# Due_Shield_v1_0.net
KiCad netlist of a schematic drawn in EAGLE
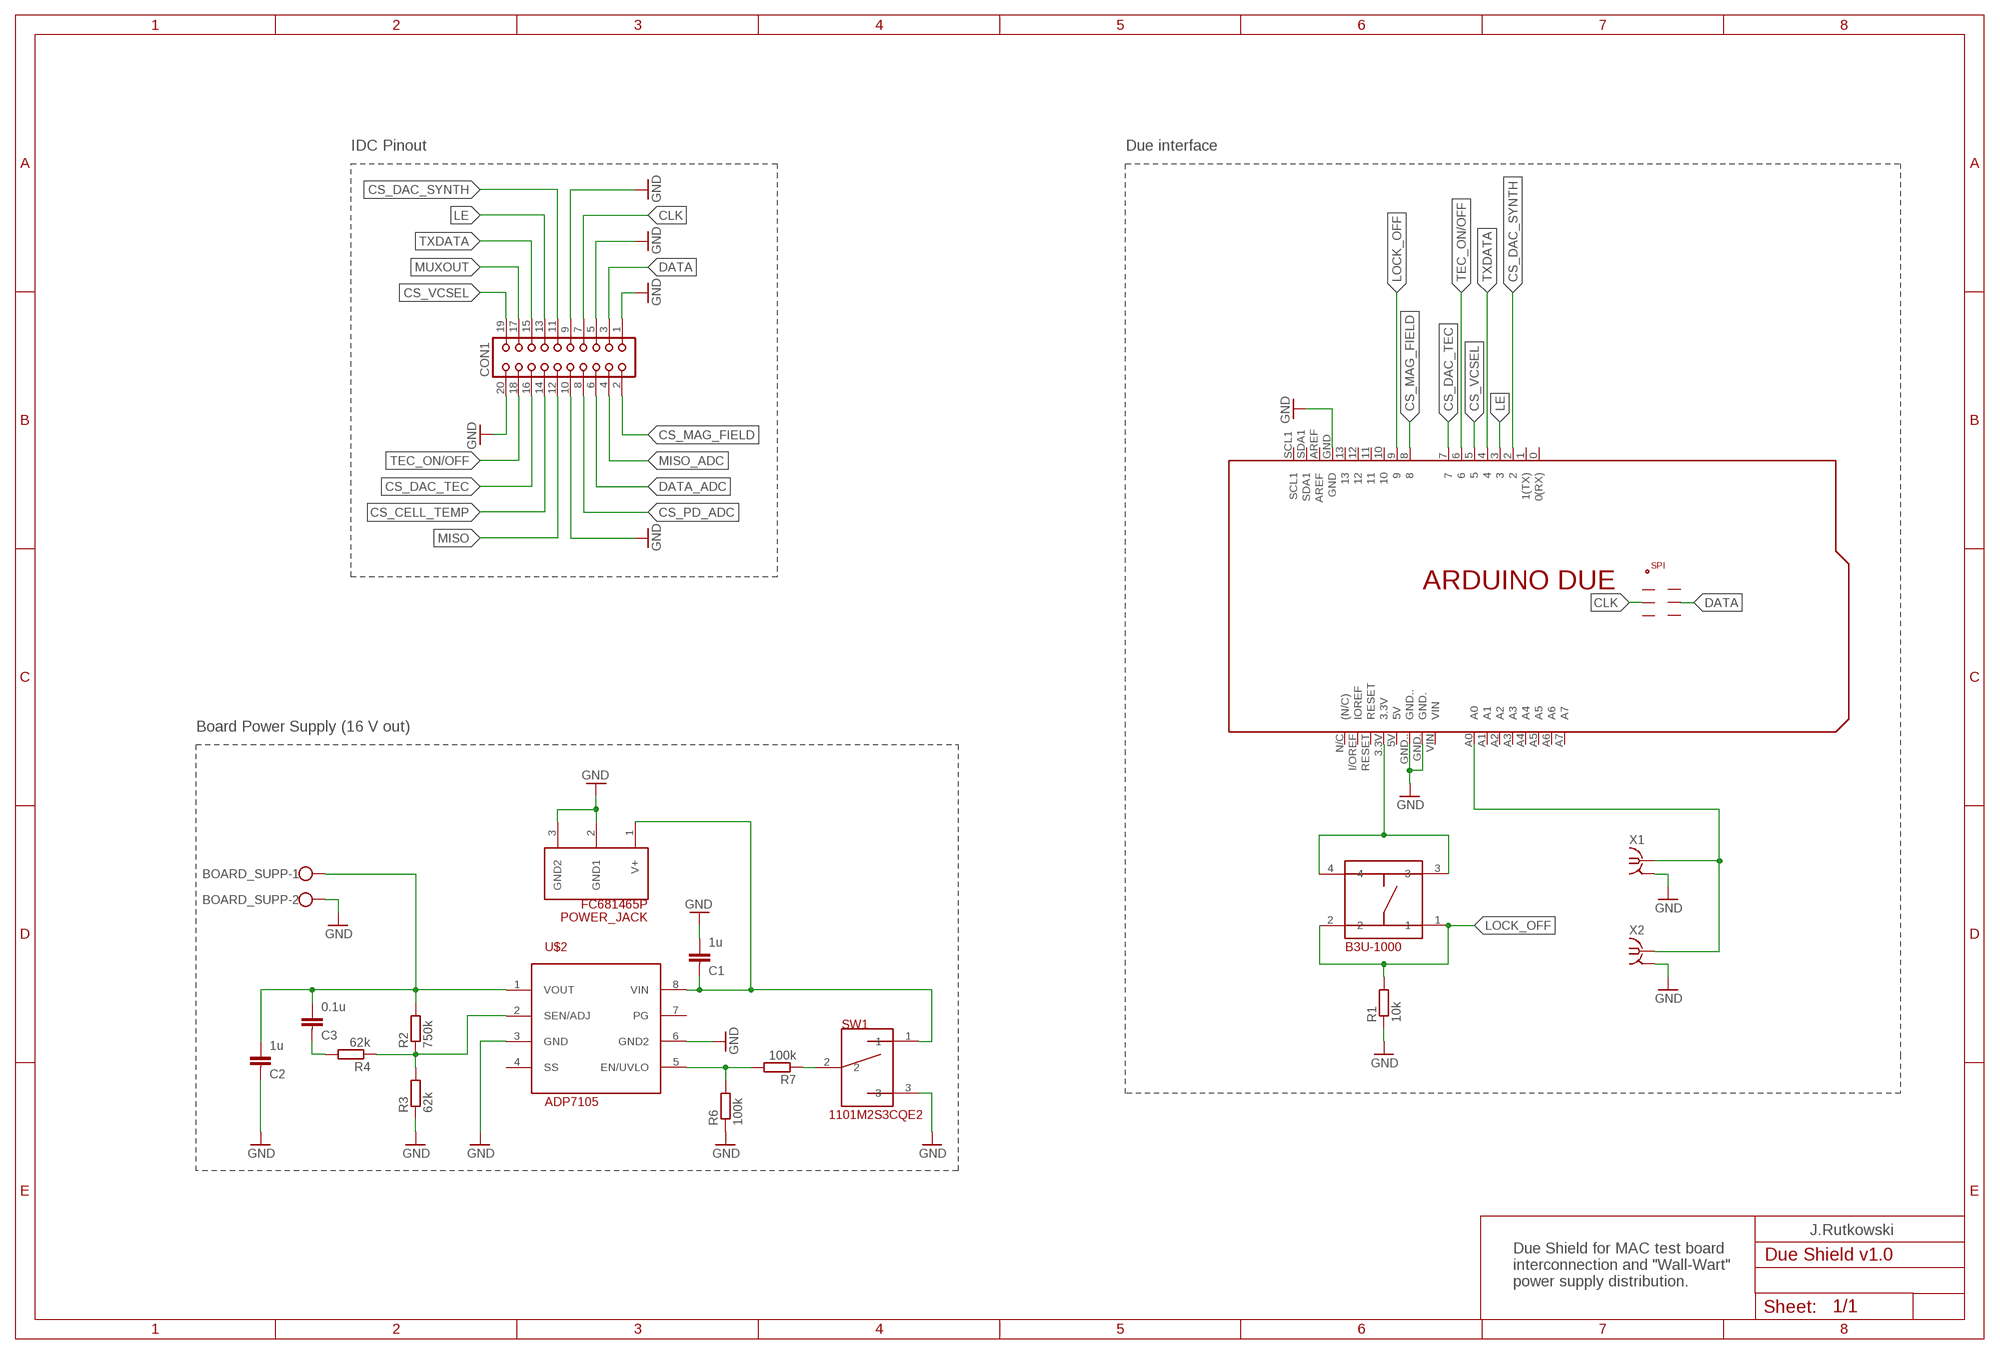
[diagram p0: schematic, sheet 1]

(export (version "E")
  (design (tool "Eeschema 10.0.6"))
  (components
    (comp (ref "BOARD_SUPP")
      (value "W237-102")
      (footprint "eagle-import:W237-102")
      (fields (field (name "MPN") "237-102"))
      (libsource (lib "eagle-import") (part "W237-102"))
    )
    (comp (ref "C1")
      (value "1u")
      (footprint "eagle-import:C0805K")
      (libsource (lib "eagle-import") (part "C-EUC0805K"))
    )
    (comp (ref "C2")
      (value "1u")
      (footprint "eagle-import:C0805K")
      (libsource (lib "eagle-import") (part "C-EUC0805K"))
    )
    (comp (ref "C3")
      (value "0.1u")
      (footprint "eagle-import:C0805K")
      (libsource (lib "eagle-import") (part "C-EUC0805K"))
    )
    (comp (ref "CON1")
      (value "CON20")
      (footprint "eagle-import:CON20")
      (libsource (lib "eagle-import") (part "CON20"))
    )
    (comp (ref "PCB1")
      (value "ARDUINO_DUE")
      (footprint "eagle-import:ARDUINO_DUE")
      (libsource (lib "eagle-import") (part "ARDUINO_DUE"))
    )
    (comp (ref "POWER_JACK")
      (value "FC681465P")
      (footprint "eagle-import:FC681465P")
      (libsource (lib "eagle-import") (part "FC681465P"))
    )
    (comp (ref "R1")
      (value "10k")
      (footprint "eagle-import:R0603")
      (libsource (lib "eagle-import") (part "R-EU_R0603"))
    )
    (comp (ref "R2")
      (value "750k")
      (footprint "eagle-import:R0603")
      (libsource (lib "eagle-import") (part "R-EU_R0603"))
    )
    (comp (ref "R3")
      (value "62k")
      (footprint "eagle-import:R0603")
      (libsource (lib "eagle-import") (part "R-EU_R0603"))
    )
    (comp (ref "R4")
      (value "62k")
      (footprint "eagle-import:R0603")
      (libsource (lib "eagle-import") (part "R-EU_R0603"))
    )
    (comp (ref "R6")
      (value "100k")
      (footprint "eagle-import:R0603")
      (libsource (lib "eagle-import") (part "R-EU_R0603"))
    )
    (comp (ref "R7")
      (value "100k")
      (footprint "eagle-import:R0603")
      (libsource (lib "eagle-import") (part "R-EU_R0603"))
    )
    (comp (ref "SW1")
      (value "1101M2S3CQE2")
      (footprint "eagle-import:1101M2S3CQE2")
      (libsource (lib "eagle-import") (part "1101M2S3CQE2"))
    )
    (comp (ref "U$1")
      (value "B3U-1000")
      (footprint "eagle-import:B3U-1000")
      (libsource (lib "eagle-import") (part "B3U-1000"))
    )
    (comp (ref "U$2")
      (value "ADP7105")
      (footprint "eagle-import:SO8")
      (libsource (lib "eagle-import") (part "ADP7105"))
    )
    (comp (ref "X1")
      (value "BU-SMA-V")
      (footprint "eagle-import:BU-SMA-V")
      (libsource (lib "eagle-import") (part "BU-SMA-V"))
    )
    (comp (ref "X2")
      (value "BU-SMA-V")
      (footprint "eagle-import:BU-SMA-V")
      (libsource (lib "eagle-import") (part "BU-SMA-V"))
    )
  )
  (nets
    (net (code "1") (name "CLK") (class "Default")
      (node (ref "CON1") (pin "7") (pinfunction "7_7") (pintype "passive"))
      (node (ref "PCB1") (pin "SCK") (pinfunction "SCK_SCK") (pintype "bidirectional"))
    )
    (net (code "2") (name "CS_CELL_TEMP") (class "Default")
      (node (ref "CON1") (pin "14") (pinfunction "14_14") (pintype "passive"))
    )
    (net (code "3") (name "CS_DAC_SYNTH") (class "Default")
      (node (ref "CON1") (pin "11") (pinfunction "11_11") (pintype "passive"))
      (node (ref "PCB1") (pin "2") (pinfunction "2_2") (pintype "bidirectional"))
    )
    (net (code "4") (name "CS_DAC_TEC") (class "Default")
      (node (ref "CON1") (pin "16") (pinfunction "16_16") (pintype "passive"))
      (node (ref "PCB1") (pin "7") (pinfunction "7_7") (pintype "bidirectional"))
    )
    (net (code "5") (name "CS_MAG_FIELD") (class "Default")
      (node (ref "CON1") (pin "2") (pinfunction "2_2") (pintype "passive"))
      (node (ref "PCB1") (pin "8") (pinfunction "8_8") (pintype "bidirectional"))
    )
    (net (code "6") (name "CS_PD_ADC") (class "Default")
      (node (ref "CON1") (pin "8") (pinfunction "8_8") (pintype "passive"))
    )
    (net (code "7") (name "CS_VCSEL") (class "Default")
      (node (ref "CON1") (pin "19") (pinfunction "19_19") (pintype "passive"))
      (node (ref "PCB1") (pin "5") (pinfunction "5_5") (pintype "bidirectional"))
    )
    (net (code "8") (name "DATA") (class "Default")
      (node (ref "CON1") (pin "3") (pinfunction "3_3") (pintype "passive"))
      (node (ref "PCB1") (pin "MOSI") (pinfunction "MOSI_MOSI") (pintype "bidirectional"))
    )
    (net (code "9") (name "DATA_ADC") (class "Default")
      (node (ref "CON1") (pin "6") (pinfunction "6_6") (pintype "passive"))
    )
    (net (code "10") (name "GND") (class "Default")
      (node (ref "BOARD_SUPP") (pin "2") (pinfunction "KL_2") (pintype "passive"))
      (node (ref "C1") (pin "1") (pinfunction "1_1") (pintype "passive"))
      (node (ref "C2") (pin "2") (pinfunction "2_2") (pintype "passive"))
      (node (ref "CON1") (pin "1") (pinfunction "1_1") (pintype "passive"))
      (node (ref "CON1") (pin "10") (pinfunction "10_10") (pintype "passive"))
      (node (ref "CON1") (pin "20") (pinfunction "20_20") (pintype "passive"))
      (node (ref "CON1") (pin "5") (pinfunction "5_5") (pintype "passive"))
      (node (ref "CON1") (pin "9") (pinfunction "9_9") (pintype "passive"))
      (node (ref "PCB1") (pin "GND") (pinfunction "GND_GND") (pintype "bidirectional"))
      (node (ref "PCB1") (pin "GND.") (pinfunction "GND._GND.") (pintype "bidirectional"))
      (node (ref "PCB1") (pin "GND..") (pinfunction "GND.._GND..") (pintype "bidirectional"))
      (node (ref "POWER_JACK") (pin "2") (pinfunction "GND1_2") (pintype "bidirectional"))
      (node (ref "POWER_JACK") (pin "3") (pinfunction "GND2_3") (pintype "bidirectional"))
      (node (ref "R1") (pin "1") (pinfunction "1_1") (pintype "passive"))
      (node (ref "R3") (pin "1") (pinfunction "1_1") (pintype "passive"))
      (node (ref "R6") (pin "1") (pinfunction "1_1") (pintype "passive"))
      (node (ref "SW1") (pin "3") (pinfunction "3_3") (pintype "bidirectional"))
      (node (ref "U$2") (pin "3") (pinfunction "GND_3") (pintype "bidirectional"))
      (node (ref "U$2") (pin "6") (pinfunction "GND2_6") (pintype "bidirectional"))
      (node (ref "X1") (pin "2") (pinfunction "2_2") (pintype "passive"))
      (node (ref "X1") (pin "3") (pinfunction "2_3") (pintype "passive"))
      (node (ref "X1") (pin "4") (pinfunction "2_4") (pintype "passive"))
      (node (ref "X1") (pin "5") (pinfunction "2_5") (pintype "passive"))
      (node (ref "X2") (pin "2") (pinfunction "2_2") (pintype "passive"))
      (node (ref "X2") (pin "3") (pinfunction "2_3") (pintype "passive"))
      (node (ref "X2") (pin "4") (pinfunction "2_4") (pintype "passive"))
      (node (ref "X2") (pin "5") (pinfunction "2_5") (pintype "passive"))
    )
    (net (code "11") (name "LE") (class "Default")
      (node (ref "CON1") (pin "13") (pinfunction "13_13") (pintype "passive"))
      (node (ref "PCB1") (pin "3") (pinfunction "3_3") (pintype "bidirectional"))
    )
    (net (code "12") (name "LOCK_OFF") (class "Default")
      (node (ref "PCB1") (pin "9") (pinfunction "9_9") (pintype "bidirectional"))
      (node (ref "R1") (pin "2") (pinfunction "2_2") (pintype "passive"))
      (node (ref "U$1") (pin "1") (pinfunction "1_1") (pintype "bidirectional"))
      (node (ref "U$1") (pin "2") (pinfunction "2_2") (pintype "bidirectional"))
    )
    (net (code "13") (name "MISO") (class "Default")
      (node (ref "CON1") (pin "12") (pinfunction "12_12") (pintype "passive"))
    )
    (net (code "14") (name "MISO_ADC") (class "Default")
      (node (ref "CON1") (pin "4") (pinfunction "4_4") (pintype "passive"))
    )
    (net (code "15") (name "MUXOUT") (class "Default")
      (node (ref "CON1") (pin "17") (pinfunction "17_17") (pintype "passive"))
    )
    (net (code "16") (name "Net-(BOARD_SUPPA-KL)") (class "Default")
      (node (ref "BOARD_SUPP") (pin "1") (pinfunction "KL_1") (pintype "passive"))
      (node (ref "C2") (pin "1") (pinfunction "1_1") (pintype "passive"))
      (node (ref "C3") (pin "1") (pinfunction "1_1") (pintype "passive"))
      (node (ref "R2") (pin "2") (pinfunction "2_2") (pintype "passive"))
      (node (ref "U$2") (pin "1") (pinfunction "VOUT_1") (pintype "bidirectional"))
    )
    (net (code "17") (name "Net-(C3-Pad2)") (class "Default")
      (node (ref "C3") (pin "2") (pinfunction "2_2") (pintype "passive"))
      (node (ref "R4") (pin "2") (pinfunction "2_2") (pintype "passive"))
    )
    (net (code "18") (name "Net-(PCB1-Pad3.3V)") (class "Default")
      (node (ref "PCB1") (pin "3.3V") (pinfunction "3.3V_3.3V") (pintype "bidirectional"))
      (node (ref "U$1") (pin "3") (pinfunction "3_3") (pintype "bidirectional"))
      (node (ref "U$1") (pin "4") (pinfunction "4_4") (pintype "bidirectional"))
    )
    (net (code "19") (name "Net-(PCB1-PadA0)") (class "Default")
      (node (ref "PCB1") (pin "A0") (pinfunction "A0_A0") (pintype "bidirectional"))
      (node (ref "X1") (pin "1") (pinfunction "1_1") (pintype "passive"))
      (node (ref "X2") (pin "1") (pinfunction "1_1") (pintype "passive"))
    )
    (net (code "20") (name "Net-(POWER_JACK-V+)") (class "Default")
      (node (ref "C1") (pin "2") (pinfunction "2_2") (pintype "passive"))
      (node (ref "POWER_JACK") (pin "1") (pinfunction "V+_1") (pintype "bidirectional"))
      (node (ref "SW1") (pin "1") (pinfunction "1_1") (pintype "bidirectional"))
      (node (ref "U$2") (pin "8") (pinfunction "VIN_8") (pintype "bidirectional"))
    )
    (net (code "21") (name "Net-(R7-Pad1)") (class "Default")
      (node (ref "R7") (pin "1") (pinfunction "1_1") (pintype "passive"))
      (node (ref "SW1") (pin "2") (pinfunction "2_2") (pintype "bidirectional"))
    )
    (net (code "22") (name "Net-(U$2-EN{slash}UVLO)") (class "Default")
      (node (ref "R6") (pin "2") (pinfunction "2_2") (pintype "passive"))
      (node (ref "R7") (pin "2") (pinfunction "2_2") (pintype "passive"))
      (node (ref "U$2") (pin "5") (pinfunction "EN/UVLO_5") (pintype "bidirectional"))
    )
    (net (code "23") (name "Net-(U$2-SEN{slash}ADJ)") (class "Default")
      (node (ref "R2") (pin "1") (pinfunction "1_1") (pintype "passive"))
      (node (ref "R3") (pin "2") (pinfunction "2_2") (pintype "passive"))
      (node (ref "R4") (pin "1") (pinfunction "1_1") (pintype "passive"))
      (node (ref "U$2") (pin "2") (pinfunction "SEN/ADJ_2") (pintype "bidirectional"))
    )
    (net (code "24") (name "TEC_ON{slash}OFF") (class "Default")
      (node (ref "CON1") (pin "18") (pinfunction "18_18") (pintype "passive"))
      (node (ref "PCB1") (pin "6") (pinfunction "6_6") (pintype "bidirectional"))
    )
    (net (code "25") (name "TXDATA") (class "Default")
      (node (ref "CON1") (pin "15") (pinfunction "15_15") (pintype "passive"))
      (node (ref "PCB1") (pin "4") (pinfunction "4_4") (pintype "bidirectional"))
    )
    (net (code "26") (name "unconnected-(PCB1-(N{slash}C)-PadN{slash}C)") (class "Default")
      (node (ref "PCB1") (pin "N/C") (pinfunction "(N/C)_N/C") (pintype "bidirectional"))
    )
    (net (code "27") (name "unconnected-(PCB1-0(RX)-Pad0)") (class "Default")
      (node (ref "PCB1") (pin "0") (pinfunction "0(RX)_0") (pintype "bidirectional"))
    )
    (net (code "28") (name "unconnected-(PCB1-1(TX)-Pad1)") (class "Default")
      (node (ref "PCB1") (pin "1") (pinfunction "1(TX)_1") (pintype "bidirectional"))
    )
    (net (code "29") (name "unconnected-(PCB1-IOREF-PadI{slash}OREF)") (class "Default")
      (node (ref "PCB1") (pin "I/OREF") (pinfunction "IOREF_I/OREF") (pintype "bidirectional"))
    )
    (net (code "30") (name "unconnected-(PCB1-Pad+5V_)") (class "Default")
      (node (ref "PCB1") (pin "+5V_") (pinfunction "+5V__+5V_") (pintype "bidirectional"))
    )
    (net (code "31") (name "unconnected-(PCB1-Pad5V)") (class "Default")
      (node (ref "PCB1") (pin "5V") (pinfunction "5V_5V") (pintype "bidirectional"))
    )
    (net (code "32") (name "unconnected-(PCB1-Pad10)") (class "Default")
      (node (ref "PCB1") (pin "10") (pinfunction "10_10") (pintype "bidirectional"))
    )
    (net (code "33") (name "unconnected-(PCB1-Pad11)") (class "Default")
      (node (ref "PCB1") (pin "11") (pinfunction "11_11") (pintype "bidirectional"))
    )
    (net (code "34") (name "unconnected-(PCB1-Pad12)") (class "Default")
      (node (ref "PCB1") (pin "12") (pinfunction "12_12") (pintype "bidirectional"))
    )
    (net (code "35") (name "unconnected-(PCB1-Pad13)") (class "Default")
      (node (ref "PCB1") (pin "13") (pinfunction "13_13") (pintype "bidirectional"))
    )
    (net (code "36") (name "unconnected-(PCB1-PadA1)") (class "Default")
      (node (ref "PCB1") (pin "A1") (pinfunction "A1_A1") (pintype "bidirectional"))
    )
    (net (code "37") (name "unconnected-(PCB1-PadA2)") (class "Default")
      (node (ref "PCB1") (pin "A2") (pinfunction "A2_A2") (pintype "bidirectional"))
    )
    (net (code "38") (name "unconnected-(PCB1-PadA3)") (class "Default")
      (node (ref "PCB1") (pin "A3") (pinfunction "A3_A3") (pintype "bidirectional"))
    )
    (net (code "39") (name "unconnected-(PCB1-PadA4)") (class "Default")
      (node (ref "PCB1") (pin "A4") (pinfunction "A4_A4") (pintype "bidirectional"))
    )
    (net (code "40") (name "unconnected-(PCB1-PadA5)") (class "Default")
      (node (ref "PCB1") (pin "A5") (pinfunction "A5_A5") (pintype "bidirectional"))
    )
    (net (code "41") (name "unconnected-(PCB1-PadA6)") (class "Default")
      (node (ref "PCB1") (pin "A6") (pinfunction "A6_A6") (pintype "bidirectional"))
    )
    (net (code "42") (name "unconnected-(PCB1-PadA7)") (class "Default")
      (node (ref "PCB1") (pin "A7") (pinfunction "A7_A7") (pintype "bidirectional"))
    )
    (net (code "43") (name "unconnected-(PCB1-PadAREF)") (class "Default")
      (node (ref "PCB1") (pin "AREF") (pinfunction "AREF_AREF") (pintype "bidirectional"))
    )
    (net (code "44") (name "unconnected-(PCB1-PadGND__)") (class "Default")
      (node (ref "PCB1") (pin "GND__") (pinfunction "GND___GND__") (pintype "bidirectional"))
    )
    (net (code "45") (name "unconnected-(PCB1-PadMISO)") (class "Default")
      (node (ref "PCB1") (pin "MISO") (pinfunction "MISO_MISO") (pintype "bidirectional"))
    )
    (net (code "46") (name "unconnected-(PCB1-PadRESET)") (class "Default")
      (node (ref "PCB1") (pin "RESET") (pinfunction "RESET_RESET") (pintype "bidirectional"))
    )
    (net (code "47") (name "unconnected-(PCB1-PadRESET.)") (class "Default")
      (node (ref "PCB1") (pin "RESET.") (pinfunction "RESET._RESET.") (pintype "bidirectional"))
    )
    (net (code "48") (name "unconnected-(PCB1-PadSCL1)") (class "Default")
      (node (ref "PCB1") (pin "SCL1") (pinfunction "SCL1_SCL1") (pintype "bidirectional"))
    )
    (net (code "49") (name "unconnected-(PCB1-PadSDA1)") (class "Default")
      (node (ref "PCB1") (pin "SDA1") (pinfunction "SDA1_SDA1") (pintype "bidirectional"))
    )
    (net (code "50") (name "unconnected-(PCB1-PadVIN)") (class "Default")
      (node (ref "PCB1") (pin "VIN") (pinfunction "VIN_VIN") (pintype "bidirectional"))
    )
    (net (code "51") (name "unconnected-(U$2-PG-Pad7)") (class "Default")
      (node (ref "U$2") (pin "7") (pinfunction "PG_7") (pintype "bidirectional"))
    )
    (net (code "52") (name "unconnected-(U$2-SS-Pad4)") (class "Default")
      (node (ref "U$2") (pin "4") (pinfunction "SS_4") (pintype "bidirectional"))
    )
  )
)
